# 1_Power_Path.net
KiCad netlist of a schematic drawn in Altium Designer
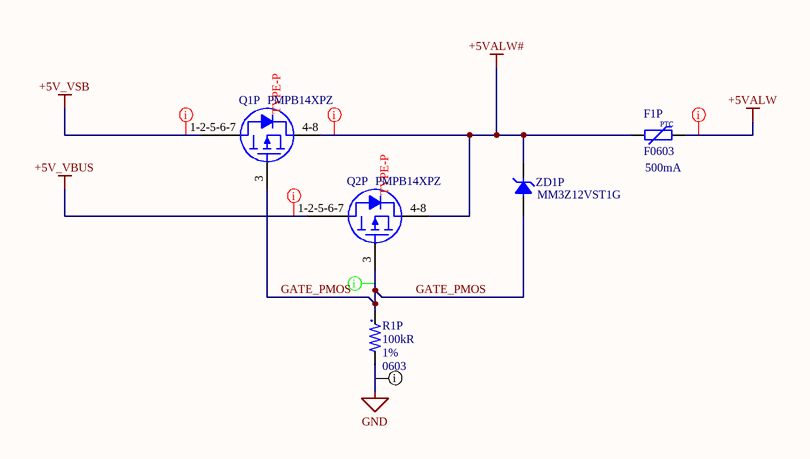
[diagram p0: 1_Power_Path.SchDoc]

(export (version "E")
  (design (tool "Eeschema 10.0.6"))
  (components
    (comp (ref "F1P")
      (value "F0603")
      (footprint "R0603-IPC_C")
      (description "Fuse PPTC SMD 0603")
      (fields (field (name "ALTIUM_VALUE") "500mA"))
      (libsource (lib "Lib_Fuse") (part "FUSE_PPTC_0603"))
    )
    (comp (ref "Q1P")
      (value "PMPB14XPZ")
      (footprint "DFN2020MD-MFG")
      (fields (field (name "MANUFACTURER") "Nexperia"))
      (libsource (lib "Lib_Mosfet_PNP") (part "PMPB14XPZ"))
    )
    (comp (ref "Q2P")
      (value "PMPB14XPZ")
      (footprint "DFN2020MD-MFG")
      (fields (field (name "MANUFACTURER") "Nexperia"))
      (libsource (lib "Lib_Mosfet_PNP") (part "PMPB14XPZ"))
    )
    (comp (ref "R1P")
      (value "100kR")
      (footprint "R0603-MFG")
      (description "SMD Chip Resistor, 100 kOhm, ± 1%, 100 mW, 0603 [1608 Metric], Thick Film, General Purpose")
      (fields
        (field (name "MANUFACTURER") "Yageo")
        (field (name "MANUFACTURER PART NUMBER") "AC0603FR-07100KL")
        (field (name "TOLERANCE") "1%")
        (field (name "CASE/PACKAGE") "0603")
      )
      (libsource (lib "Lib_Register_0603") (part "100K"))
    )
    (comp (ref "ZD1P")
      (value "MM3Z12VST1G")
      (footprint "SOD-323")
      (description "MM3Z12VST1G Zener Diode, 12V 2% 200 mW SMT 2-Pin SOD-323 ¦ ON Semiconductor MM3Z12VST1G")
      (fields (field (name "MANUFACTURER") "ON Semiconductor") (field (name "TOLERANCE") "2%"))
      (libsource (lib "Lib_Diodes") (part "MM3Z12VST1G"))
    )
  )
  (nets
    (net (code "1") (name "+5VALW") (class "Default")
      (node (ref "F1P") (pin "2") (pinfunction "2_2") (pintype "passive"))
    )
    (net (code "2") (name "+5VALW#") (class "Default")
      (node (ref "F1P") (pin "1") (pinfunction "1_1") (pintype "passive"))
      (node (ref "Q1P") (pin "4-8") (pinfunction "S_4-8") (pintype "passive"))
      (node (ref "Q2P") (pin "4-8") (pinfunction "S_4-8") (pintype "passive"))
      (node (ref "ZD1P") (pin "1") (pinfunction "C_1") (pintype "passive"))
    )
    (net (code "3") (name "+5V_VBUS") (class "Default")
      (node (ref "Q2P") (pin "1-2-5-6-7") (pinfunction "D_1-2-5-6-7") (pintype "passive"))
    )
    (net (code "4") (name "+5V_VSB") (class "Default")
      (node (ref "Q1P") (pin "1-2-5-6-7") (pinfunction "D_1-2-5-6-7") (pintype "passive"))
    )
    (net (code "5") (name "/GATE_PMOS") (class "Default")
      (node (ref "Q1P") (pin "3") (pinfunction "G_3") (pintype "passive"))
      (node (ref "Q2P") (pin "3") (pinfunction "G_3") (pintype "passive"))
      (node (ref "R1P") (pin "1") (pinfunction "1_1") (pintype "passive"))
      (node (ref "ZD1P") (pin "2") (pinfunction "A_2") (pintype "passive"))
    )
    (net (code "6") (name "GND") (class "Default")
      (node (ref "R1P") (pin "2") (pinfunction "2_2") (pintype "passive"))
    )
  )
)
